# Segnalino.net
KiCad netlist of a schematic drawn in EAGLE
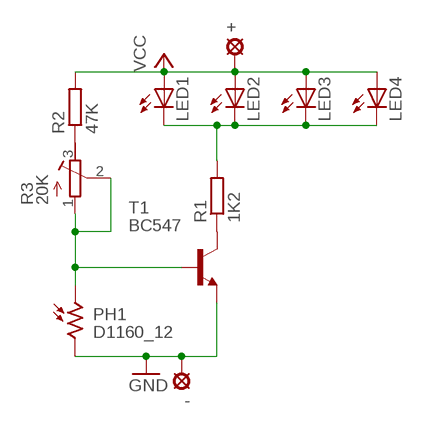
[diagram p0: schematic, sheet 1]

(export (version "E")
  (design (tool "Eeschema 10.0.6"))
  (components
    (comp (ref "+")
      (value "LSP10")
      (footprint "eagle-import:LSP10")
      (libsource (lib "eagle-import") (part "LSP10"))
    )
    (comp (ref "-")
      (value "LSP10")
      (footprint "eagle-import:LSP10")
      (libsource (lib "eagle-import") (part "LSP10"))
    )
    (comp (ref "LED1")
      (value "LED10MM")
      (footprint "eagle-import:LED10MM")
      (libsource (lib "eagle-import") (part "LED10MM"))
    )
    (comp (ref "LED2")
      (value "LED10MM")
      (footprint "eagle-import:LED10MM")
      (libsource (lib "eagle-import") (part "LED10MM"))
    )
    (comp (ref "LED3")
      (value "LED10MM")
      (footprint "eagle-import:LED10MM")
      (libsource (lib "eagle-import") (part "LED10MM"))
    )
    (comp (ref "LED4")
      (value "LED10MM")
      (footprint "eagle-import:LED10MM")
      (libsource (lib "eagle-import") (part "LED10MM"))
    )
    (comp (ref "PH1")
      (value "D1160_12")
      (footprint "eagle-import:D11XX")
      (libsource (lib "eagle-import") (part "D1160_12"))
    )
    (comp (ref "R1")
      (value "1K2")
      (footprint "eagle-import:0204V")
      (libsource (lib "eagle-import") (part "R-EU_0204/2V"))
    )
    (comp (ref "R2")
      (value "47K")
      (footprint "eagle-import:0204V")
      (libsource (lib "eagle-import") (part "R-EU_0204/2V"))
    )
    (comp (ref "R3")
      (value "20K")
      (footprint "eagle-import:RTRIM3339P")
      (libsource (lib "eagle-import") (part "R-TRIMM3339P"))
    )
    (comp (ref "T1")
      (value "BC547")
      (footprint "eagle-import:TO92")
      (libsource (lib "eagle-import") (part "BC547"))
    )
  )
  (nets
    (net (code "1") (name "GND") (class "Default")
      (node (ref "-") (pin "MP") (pinfunction "MP_MP") (pintype "passive"))
      (node (ref "PH1") (pin "2") (pinfunction "2_2") (pintype "passive"))
      (node (ref "T1") (pin "1") (pinfunction "E_1") (pintype "passive"))
    )
    (net (code "2") (name "Net-(LED1-C)") (class "Default")
      (node (ref "LED1") (pin "K") (pinfunction "C_K") (pintype "passive"))
      (node (ref "LED2") (pin "K") (pinfunction "C_K") (pintype "passive"))
      (node (ref "LED3") (pin "K") (pinfunction "C_K") (pintype "passive"))
      (node (ref "LED4") (pin "K") (pinfunction "C_K") (pintype "passive"))
      (node (ref "R1") (pin "2") (pinfunction "2_2") (pintype "passive"))
    )
    (net (code "3") (name "Net-(R3-A)") (class "Default")
      (node (ref "PH1") (pin "1") (pinfunction "1_1") (pintype "passive"))
      (node (ref "R3") (pin "1") (pinfunction "A_1") (pintype "passive"))
      (node (ref "R3") (pin "2") (pinfunction "S_2") (pintype "passive"))
      (node (ref "T1") (pin "2") (pinfunction "B_2") (pintype "passive"))
    )
    (net (code "4") (name "Net-(R3-E)") (class "Default")
      (node (ref "R2") (pin "1") (pinfunction "1_1") (pintype "passive"))
      (node (ref "R3") (pin "3") (pinfunction "E_3") (pintype "passive"))
    )
    (net (code "5") (name "Net-(T1-C)") (class "Default")
      (node (ref "R1") (pin "1") (pinfunction "1_1") (pintype "passive"))
      (node (ref "T1") (pin "3") (pinfunction "C_3") (pintype "passive"))
    )
    (net (code "6") (name "VCC") (class "Default")
      (node (ref "+") (pin "MP") (pinfunction "MP_MP") (pintype "passive"))
      (node (ref "LED1") (pin "A") (pinfunction "A_A") (pintype "passive"))
      (node (ref "LED2") (pin "A") (pinfunction "A_A") (pintype "passive"))
      (node (ref "LED3") (pin "A") (pinfunction "A_A") (pintype "passive"))
      (node (ref "LED4") (pin "A") (pinfunction "A_A") (pintype "passive"))
      (node (ref "R2") (pin "2") (pinfunction "2_2") (pintype "passive"))
    )
  )
)
